# Schematic.net
KiCad netlist of a schematic drawn in EAGLE
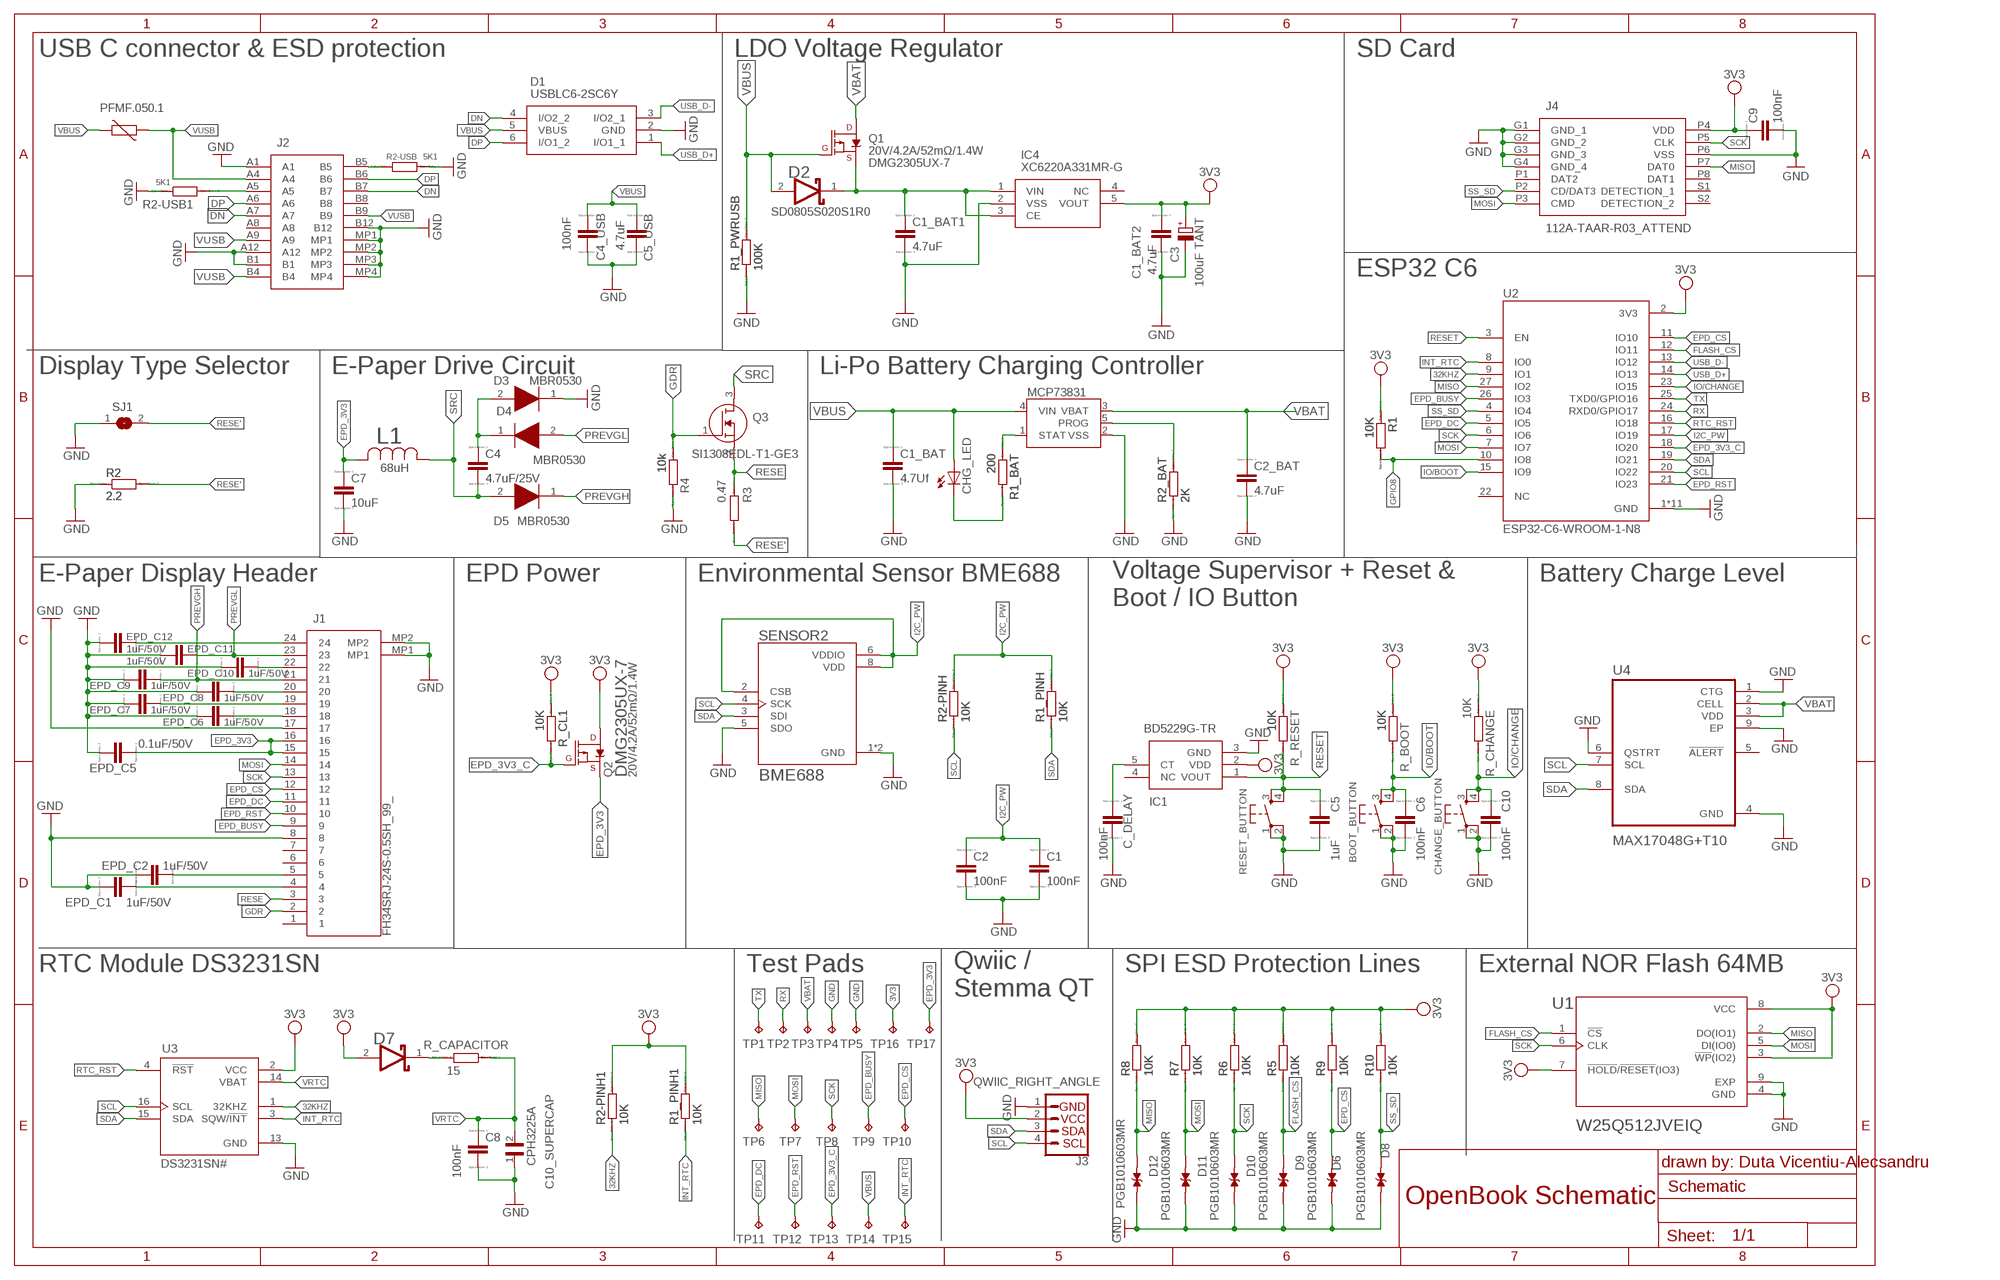
[diagram p0: schematic, sheet 1]

(export (version "E")
  (design (tool "Eeschema 10.0.6"))
  (components
    (comp (ref "BOOT_BUTTON")
      (value "BUTTON_CUSYOMV1")
      (footprint "eagle-import:MYBUTTON")
      (libsource (lib "eagle-import") (part "BUTTON_CUSYOMV1"))
    )
    (comp (ref "C1")
      (value "100nF")
      (footprint "eagle-import:EAGLE-LTSPICE_C0402")
      (libsource (lib "eagle-import") (part "EAGLE-LTSPICE_CC0402"))
    )
    (comp (ref "C1_BAT")
      (value "4.7Uf")
      (footprint "eagle-import:EAGLE-LTSPICE_C0402")
      (libsource (lib "eagle-import") (part "EAGLE-LTSPICE_CC0402"))
    )
    (comp (ref "C1_BAT1")
      (value "4.7uF")
      (footprint "eagle-import:EAGLE-LTSPICE_C0402")
      (libsource (lib "eagle-import") (part "EAGLE-LTSPICE_CC0402"))
    )
    (comp (ref "C1_BAT2")
      (value "4.7uF")
      (footprint "eagle-import:EAGLE-LTSPICE_C0402")
      (libsource (lib "eagle-import") (part "EAGLE-LTSPICE_CC0402"))
    )
    (comp (ref "C2")
      (value "100nF")
      (footprint "eagle-import:EAGLE-LTSPICE_C0402")
      (libsource (lib "eagle-import") (part "EAGLE-LTSPICE_CC0402"))
    )
    (comp (ref "C2_BAT")
      (value "4.7uF")
      (footprint "eagle-import:EAGLE-LTSPICE_C0402")
      (libsource (lib "eagle-import") (part "EAGLE-LTSPICE_CC0402"))
    )
    (comp (ref "C3")
      (value "100uF TANT")
      (footprint "eagle-import:RCL_CT3528")
      (libsource (lib "eagle-import") (part "RCL_CPOL-EUCT3528"))
    )
    (comp (ref "C4")
      (value "4.7uF/25V")
      (footprint "eagle-import:EAGLE-LTSPICE_C0402")
      (libsource (lib "eagle-import") (part "EAGLE-LTSPICE_CC0402"))
    )
    (comp (ref "C4_USB")
      (value "100nF")
      (footprint "eagle-import:EAGLE-LTSPICE_C0402")
      (libsource (lib "eagle-import") (part "EAGLE-LTSPICE_CC0402"))
    )
    (comp (ref "C5")
      (value "1uF")
      (footprint "eagle-import:EAGLE-LTSPICE_C0402")
      (libsource (lib "eagle-import") (part "EAGLE-LTSPICE_CC0402"))
    )
    (comp (ref "C5_USB")
      (value "4.7uF")
      (footprint "eagle-import:EAGLE-LTSPICE_C0402")
      (libsource (lib "eagle-import") (part "EAGLE-LTSPICE_CC0402"))
    )
    (comp (ref "C6")
      (value "100nF")
      (footprint "eagle-import:EAGLE-LTSPICE_C0402")
      (libsource (lib "eagle-import") (part "EAGLE-LTSPICE_CC0402"))
    )
    (comp (ref "C7")
      (value "10uF")
      (footprint "eagle-import:EAGLE-LTSPICE_C0402")
      (libsource (lib "eagle-import") (part "EAGLE-LTSPICE_CC0402"))
    )
    (comp (ref "C8")
      (value "100nF")
      (footprint "eagle-import:EAGLE-LTSPICE_C0402")
      (libsource (lib "eagle-import") (part "EAGLE-LTSPICE_CC0402"))
    )
    (comp (ref "C9")
      (value "100nF")
      (footprint "eagle-import:EAGLE-LTSPICE_C0402")
      (libsource (lib "eagle-import") (part "EAGLE-LTSPICE_CC0402"))
    )
    (comp (ref "C10")
      (value "100nF")
      (footprint "eagle-import:EAGLE-LTSPICE_C0402")
      (libsource (lib "eagle-import") (part "EAGLE-LTSPICE_CC0402"))
    )
    (comp (ref "C10_SUPERCAP")
      (value "CPH3225A")
      (footprint "eagle-import:CAPCP3225X100N")
      (fields (field (name "MF") "Seiko Instruments"))
      (libsource (lib "eagle-import") (part "CPH3225A"))
    )
    (comp (ref "CHANGE_BUTTON")
      (value "BUTTON_CUSYOMV1")
      (footprint "eagle-import:MYBUTTON")
      (libsource (lib "eagle-import") (part "BUTTON_CUSYOMV1"))
    )
    (comp (ref "CHG_LED")
      (value "ADAFRUIT_LEDCHIP-LED0603")
      (footprint "eagle-import:ADAFRUIT_CHIP-LED0603")
      (libsource (lib "eagle-import") (part "ADAFRUIT_LEDCHIP-LED0603"))
    )
    (comp (ref "C_DELAY")
      (value "100nF")
      (footprint "eagle-import:EAGLE-LTSPICE_C0402")
      (libsource (lib "eagle-import") (part "EAGLE-LTSPICE_CC0402"))
    )
    (comp (ref "D1")
      (value "USBLC6-2SC6Y")
      (footprint "eagle-import:SOT95P280X145-6N")
      (fields (field (name "MF") "STMicroelectronics"))
      (libsource (lib "eagle-import") (part "USBLC6-2SC6Y"))
    )
    (comp (ref "D2")
      (value "ESP32_WROVER_AVX---SD0805S020S1R0_AVX_SD0805S020S1R0_0_0AVX_SD0805S020S1R0_0_0")
      (footprint "eagle-import:ESP32_WROVER_AVX---SD0805S020S1R0_AVX_SD0805S020S1R0_0")
      (fields
        (field (name "DIGIKEY_PART_NUMBER") "478-7800-1-ND")
        (field (name "MF") "AVX")
        (field (name "MOUSER_PART_NUMBER") "581-SD0805S020S1R0")
      )
      (libsource (lib "eagle-import") (part "ESP32_WROVER_AVX---SD0805S020S1R0_AVX_SD0805S020S1R0_0_0AVX_SD0805S020S1R0_0_0"))
    )
    (comp (ref "D3")
      (value "MBR0530")
      (footprint "eagle-import:SOD3716X135N")
      (fields (field (name "MF") "ON Semiconductor"))
      (libsource (lib "eagle-import") (part "MBR0530"))
    )
    (comp (ref "D4")
      (value "MBR0530")
      (footprint "eagle-import:SOD3716X135N")
      (fields (field (name "MF") "ON Semiconductor"))
      (libsource (lib "eagle-import") (part "MBR0530"))
    )
    (comp (ref "D5")
      (value "MBR0530")
      (footprint "eagle-import:SOD3716X135N")
      (fields (field (name "MF") "ON Semiconductor"))
      (libsource (lib "eagle-import") (part "MBR0530"))
    )
    (comp (ref "D6")
      (value "PGB1010603MR")
      (footprint "eagle-import:DIOC1608X36N")
      (fields (field (name "MF") "Littelfuse Inc."))
      (libsource (lib "eagle-import") (part "PGB1010603MR"))
    )
    (comp (ref "D7")
      (value "ESP32_WROVER_AVX---SD0805S020S1R0_AVX_SD0805S020S1R0_0_0AVX_SD0805S020S1R0_0_0")
      (footprint "eagle-import:ESP32_WROVER_AVX---SD0805S020S1R0_AVX_SD0805S020S1R0_0")
      (fields
        (field (name "DIGIKEY_PART_NUMBER") "478-7800-1-ND")
        (field (name "MF") "AVX")
        (field (name "MOUSER_PART_NUMBER") "581-SD0805S020S1R0")
      )
      (libsource (lib "eagle-import") (part "ESP32_WROVER_AVX---SD0805S020S1R0_AVX_SD0805S020S1R0_0_0AVX_SD0805S020S1R0_0_0"))
    )
    (comp (ref "D8")
      (value "PGB1010603MR")
      (footprint "eagle-import:DIOC1608X36N")
      (fields (field (name "MF") "Littelfuse Inc."))
      (libsource (lib "eagle-import") (part "PGB1010603MR"))
    )
    (comp (ref "D9")
      (value "PGB1010603MR")
      (footprint "eagle-import:DIOC1608X36N")
      (fields (field (name "MF") "Littelfuse Inc."))
      (libsource (lib "eagle-import") (part "PGB1010603MR"))
    )
    (comp (ref "D10")
      (value "PGB1010603MR")
      (footprint "eagle-import:DIOC1608X36N")
      (fields (field (name "MF") "Littelfuse Inc."))
      (libsource (lib "eagle-import") (part "PGB1010603MR"))
    )
    (comp (ref "D11")
      (value "PGB1010603MR")
      (footprint "eagle-import:DIOC1608X36N")
      (fields (field (name "MF") "Littelfuse Inc."))
      (libsource (lib "eagle-import") (part "PGB1010603MR"))
    )
    (comp (ref "D12")
      (value "PGB1010603MR")
      (footprint "eagle-import:DIOC1608X36N")
      (fields (field (name "MF") "Littelfuse Inc."))
      (libsource (lib "eagle-import") (part "PGB1010603MR"))
    )
    (comp (ref "EPD_C1")
      (value "1uF/50V")
      (footprint "eagle-import:EAGLE-LTSPICE_C0402")
      (libsource (lib "eagle-import") (part "EAGLE-LTSPICE_CC0402"))
    )
    (comp (ref "EPD_C2")
      (value "1uF/50V")
      (footprint "eagle-import:EAGLE-LTSPICE_C0402")
      (libsource (lib "eagle-import") (part "EAGLE-LTSPICE_CC0402"))
    )
    (comp (ref "EPD_C5")
      (value "0.1uF/50V")
      (footprint "eagle-import:EAGLE-LTSPICE_C0402")
      (libsource (lib "eagle-import") (part "EAGLE-LTSPICE_CC0402"))
    )
    (comp (ref "EPD_C6")
      (value "1uF/50V")
      (footprint "eagle-import:EAGLE-LTSPICE_C0402")
      (libsource (lib "eagle-import") (part "EAGLE-LTSPICE_CC0402"))
    )
    (comp (ref "EPD_C7")
      (value "1uF/50V")
      (footprint "eagle-import:EAGLE-LTSPICE_C0402")
      (libsource (lib "eagle-import") (part "EAGLE-LTSPICE_CC0402"))
    )
    (comp (ref "EPD_C8")
      (value "1uF/50V")
      (footprint "eagle-import:EAGLE-LTSPICE_C0402")
      (libsource (lib "eagle-import") (part "EAGLE-LTSPICE_CC0402"))
    )
    (comp (ref "EPD_C9")
      (value "1uF/50V")
      (footprint "eagle-import:EAGLE-LTSPICE_C0402")
      (libsource (lib "eagle-import") (part "EAGLE-LTSPICE_CC0402"))
    )
    (comp (ref "EPD_C10")
      (value "1uF/50V")
      (footprint "eagle-import:EAGLE-LTSPICE_C0402")
      (libsource (lib "eagle-import") (part "EAGLE-LTSPICE_CC0402"))
    )
    (comp (ref "EPD_C11")
      (value "1uF/50V")
      (footprint "eagle-import:EAGLE-LTSPICE_C0402")
      (libsource (lib "eagle-import") (part "EAGLE-LTSPICE_CC0402"))
    )
    (comp (ref "EPD_C12")
      (value "1uF/50V")
      (footprint "eagle-import:EAGLE-LTSPICE_C0402")
      (libsource (lib "eagle-import") (part "EAGLE-LTSPICE_CC0402"))
    )
    (comp (ref "IC1")
      (value "BD5229G-TR")
      (footprint "eagle-import:SOT95P280X125-5N")
      (fields (field (name "MOUSER_PART_NUMBER") "755-BD5229G-TR"))
      (libsource (lib "eagle-import") (part "BD5229G-TR"))
    )
    (comp (ref "IC4")
      (value "XC6220A331MR-G")
      (footprint "eagle-import:SOT95P280X120-5N")
      (fields (field (name "MOUSER_PART_NUMBER") "865-XC6220A331MR-G"))
      (libsource (lib "eagle-import") (part "XC6220A331MR-G"))
    )
    (comp (ref "J1")
      (value "FH34SRJ-24S-0.5SH_99_")
      (footprint "eagle-import:FH34SRJ24S05SH99")
      (fields
        (field (name "MANUFACTURER_PART_NUMBER") "FH34SRJ-24S-0.5SH(99)")
        (field (name "MOUSER_PART_NUMBER") "798-FH34SRJ24S05SH99")
      )
      (libsource (lib "eagle-import") (part "FH34SRJ-24S-0.5SH_99_"))
    )
    (comp (ref "J2")
      (value "SAMACSYS_PARTS_USB4110-GF-A")
      (footprint "eagle-import:SAMACSYS_PARTS_USB4110GFA")
      (fields
        (field (name "MANUFACTURER_PART_NUMBER") "USB4110-GF-A")
        (field (name "MOUSER_PART_NUMBER") "640-USB4110-GF-A")
      )
      (libsource (lib "eagle-import") (part "SAMACSYS_PARTS_USB4110-GF-A"))
    )
    (comp (ref "J3")
      (value "QWIIC_RIGHT_ANGLE")
      (footprint "eagle-import:JST04_1MM_RA")
      (libsource (lib "eagle-import") (part "QWIIC_CONNECTORJS-1MM"))
    )
    (comp (ref "J4")
      (value "112A-TAAR-R03_ATTEND")
      (footprint "eagle-import:112ATAARR03ATTEND")
      (fields (field (name "MANUFACTURER_PART_NUMBER") "112A-TAAR-R03 ATTEND"))
      (libsource (lib "eagle-import") (part "112A-TAAR-R03_ATTEND"))
    )
    (comp (ref "L1")
      (value "744043680IND_4828-WE-TPC_WRE")
      (footprint "eagle-import:IND_4828-WE-TPC_WRE")
      (fields
        (field (name "MANUFACTURER_PART_NUMBER") "744043680")
        (field (name "COPYRIGHT") "Copyright (C) 2024 Ultra Librarian. All rights reserved.")
      )
      (libsource (lib "eagle-import") (part "744043680IND_4828-WE-TPC_WRE"))
    )
    (comp (ref "MCP73831")
      (value "ESP32_WROVER_SPARKFUN-IC-POWER_MCP73831")
      (footprint "eagle-import:ESP32_WROVER_SPARKFUN-IC-POWER_SOT23-5")
      (libsource (lib "eagle-import") (part "ESP32_WROVER_SPARKFUN-IC-POWER_MCP73831"))
    )
    (comp (ref "PFMF.050.1")
      (value "ESP32C6_VARISTORCN1812")
      (footprint "eagle-import:ESP32C6_VARISTOR_CT_CN1812")
      (libsource (lib "eagle-import") (part "ESP32C6_VARISTORCN1812"))
    )
    (comp (ref "Q1")
      (value "20V/4.2A/52mΩ/1.4W")
      (footprint "eagle-import:ESP32_WROVER_SPARKFUN-DISCRETESEMI_SOT23-3")
      (libsource (lib "eagle-import") (part "ESP32_WROVER_SPARKFUN-DISCRETESEMI_MOSFET_PCH-DMG2305UX-7"))
    )
    (comp (ref "Q2")
      (value "20V/4.2A/52mΩ/1.4W")
      (footprint "eagle-import:ESP32_WROVER_SPARKFUN-DISCRETESEMI_SOT23-3")
      (libsource (lib "eagle-import") (part "ESP32_WROVER_SPARKFUN-DISCRETESEMI_MOSFET_PCH-DMG2305UX-7"))
    )
    (comp (ref "Q3")
      (value "SI1308EDL-T1-GE3")
      (footprint "eagle-import:SOT65P210X110-3N")
      (fields (field (name "MF") "Vishay Siliconix"))
      (libsource (lib "eagle-import") (part "SI1308EDL-T1-GE3"))
    )
    (comp (ref "R1")
      (value "10K")
      (footprint "eagle-import:ESP32_WROVER_EAGLE-LTSPICE_R0402")
      (libsource (lib "eagle-import") (part "ESP32_WROVER_EAGLE-LTSPICE_RR0402"))
    )
    (comp (ref "R1_BAT")
      (value "200")
      (footprint "eagle-import:ESP32_WROVER_EAGLE-LTSPICE_R0402")
      (libsource (lib "eagle-import") (part "ESP32_WROVER_EAGLE-LTSPICE_RR0402"))
    )
    (comp (ref "R1_PINH")
      (value "10K")
      (footprint "eagle-import:ESP32_WROVER_EAGLE-LTSPICE_R0402")
      (libsource (lib "eagle-import") (part "ESP32_WROVER_EAGLE-LTSPICE_RR0402"))
    )
    (comp (ref "R1_PINH1")
      (value "10K")
      (footprint "eagle-import:ESP32_WROVER_EAGLE-LTSPICE_R0402")
      (libsource (lib "eagle-import") (part "ESP32_WROVER_EAGLE-LTSPICE_RR0402"))
    )
    (comp (ref "R1_PWRUSB")
      (value "100K")
      (footprint "eagle-import:ESP32_WROVER_EAGLE-LTSPICE_R0402")
      (libsource (lib "eagle-import") (part "ESP32_WROVER_EAGLE-LTSPICE_RR0402"))
    )
    (comp (ref "R2")
      (value "2.2")
      (footprint "eagle-import:ESP32_WROVER_EAGLE-LTSPICE_R0402")
      (libsource (lib "eagle-import") (part "ESP32_WROVER_EAGLE-LTSPICE_RR0402"))
    )
    (comp (ref "R2-PINH")
      (value "10K")
      (footprint "eagle-import:ESP32_WROVER_EAGLE-LTSPICE_R0402")
      (libsource (lib "eagle-import") (part "ESP32_WROVER_EAGLE-LTSPICE_RR0402"))
    )
    (comp (ref "R2-PINH1")
      (value "10K")
      (footprint "eagle-import:ESP32_WROVER_EAGLE-LTSPICE_R0402")
      (libsource (lib "eagle-import") (part "ESP32_WROVER_EAGLE-LTSPICE_RR0402"))
    )
    (comp (ref "R2-USB")
      (value "5K1")
      (footprint "eagle-import:ESP32_WROVER_EAGLE-LTSPICE_R0402")
      (libsource (lib "eagle-import") (part "ESP32_WROVER_EAGLE-LTSPICE_RR0402"))
    )
    (comp (ref "R2-USB1")
      (value "5K1")
      (footprint "eagle-import:ESP32_WROVER_EAGLE-LTSPICE_R0402")
      (libsource (lib "eagle-import") (part "ESP32_WROVER_EAGLE-LTSPICE_RR0402"))
    )
    (comp (ref "R2_BAT")
      (value "2K")
      (footprint "eagle-import:ESP32_WROVER_EAGLE-LTSPICE_R0402")
      (libsource (lib "eagle-import") (part "ESP32_WROVER_EAGLE-LTSPICE_RR0402"))
    )
    (comp (ref "R3")
      (value "0.47")
      (footprint "eagle-import:ESP32_WROVER_EAGLE-LTSPICE_R0402")
      (libsource (lib "eagle-import") (part "ESP32_WROVER_EAGLE-LTSPICE_RR0402"))
    )
    (comp (ref "R4")
      (value "10k")
      (footprint "eagle-import:ESP32_WROVER_EAGLE-LTSPICE_R0402")
      (libsource (lib "eagle-import") (part "ESP32_WROVER_EAGLE-LTSPICE_RR0402"))
    )
    (comp (ref "R5")
      (value "10K")
      (footprint "eagle-import:ESP32_WROVER_EAGLE-LTSPICE_R0402")
      (libsource (lib "eagle-import") (part "ESP32_WROVER_EAGLE-LTSPICE_RR0402"))
    )
    (comp (ref "R6")
      (value "10K")
      (footprint "eagle-import:ESP32_WROVER_EAGLE-LTSPICE_R0402")
      (libsource (lib "eagle-import") (part "ESP32_WROVER_EAGLE-LTSPICE_RR0402"))
    )
    (comp (ref "R7")
      (value "10K")
      (footprint "eagle-import:ESP32_WROVER_EAGLE-LTSPICE_R0402")
      (libsource (lib "eagle-import") (part "ESP32_WROVER_EAGLE-LTSPICE_RR0402"))
    )
    (comp (ref "R8")
      (value "10K")
      (footprint "eagle-import:ESP32_WROVER_EAGLE-LTSPICE_R0402")
      (libsource (lib "eagle-import") (part "ESP32_WROVER_EAGLE-LTSPICE_RR0402"))
    )
    (comp (ref "R9")
      (value "10K")
      (footprint "eagle-import:ESP32_WROVER_EAGLE-LTSPICE_R0402")
      (libsource (lib "eagle-import") (part "ESP32_WROVER_EAGLE-LTSPICE_RR0402"))
    )
    (comp (ref "R10")
      (value "10K")
      (footprint "eagle-import:ESP32_WROVER_EAGLE-LTSPICE_R0402")
      (libsource (lib "eagle-import") (part "ESP32_WROVER_EAGLE-LTSPICE_RR0402"))
    )
    (comp (ref "RESET_BUTTON")
      (value "BUTTON_CUSYOMV1")
      (footprint "eagle-import:MYBUTTON")
      (libsource (lib "eagle-import") (part "BUTTON_CUSYOMV1"))
    )
    (comp (ref "R_BOOT")
      (value "10K")
      (footprint "eagle-import:ESP32_WROVER_EAGLE-LTSPICE_R0402")
      (libsource (lib "eagle-import") (part "ESP32_WROVER_EAGLE-LTSPICE_RR0402"))
    )
    (comp (ref "R_CAPACITOR")
      (value "15")
      (footprint "eagle-import:ESP32_WROVER_EAGLE-LTSPICE_R0402")
      (libsource (lib "eagle-import") (part "ESP32_WROVER_EAGLE-LTSPICE_RR0402"))
    )
    (comp (ref "R_CHANGE")
      (value "10K")
      (footprint "eagle-import:ESP32_WROVER_EAGLE-LTSPICE_R0402")
      (libsource (lib "eagle-import") (part "ESP32_WROVER_EAGLE-LTSPICE_RR0402"))
    )
    (comp (ref "R_CL1")
      (value "10K")
      (footprint "eagle-import:ESP32_WROVER_EAGLE-LTSPICE_R0402")
      (libsource (lib "eagle-import") (part "ESP32_WROVER_EAGLE-LTSPICE_RR0402"))
    )
    (comp (ref "R_RESET")
      (value "10K")
      (footprint "eagle-import:ESP32_WROVER_EAGLE-LTSPICE_R0402")
      (libsource (lib "eagle-import") (part "ESP32_WROVER_EAGLE-LTSPICE_RR0402"))
    )
    (comp (ref "SENSOR2")
      (value "ESP32_WROVER_BME680_BME680")
      (footprint "eagle-import:ESP32_WROVER_BME680_PSON80P300X300X100-8N")
      (fields (field (name "MF") "Bosch Sensortec") (field (name "MP") "BME680"))
      (libsource (lib "eagle-import") (part "ESP32_WROVER_BME680_BME680"))
    )
    (comp (ref "SJ1") (value "SJ") (footprint "eagle-import:SJ") (libsource (lib "eagle-import") (part "SJ")))
    (comp (ref "TP1")
      (value "TPTP20R")
      (footprint "eagle-import:TP20R")
      (libsource (lib "eagle-import") (part "TPTP20R"))
    )
    (comp (ref "TP2")
      (value "TPTP20R")
      (footprint "eagle-import:TP20R")
      (libsource (lib "eagle-import") (part "TPTP20R"))
    )
    (comp (ref "TP3")
      (value "TPTP20R")
      (footprint "eagle-import:TP20R")
      (libsource (lib "eagle-import") (part "TPTP20R"))
    )
    (comp (ref "TP4")
      (value "TPTP20R")
      (footprint "eagle-import:TP20R")
      (libsource (lib "eagle-import") (part "TPTP20R"))
    )
    (comp (ref "TP5")
      (value "TPTP20R")
      (footprint "eagle-import:TP20R")
      (libsource (lib "eagle-import") (part "TPTP20R"))
    )
    (comp (ref "TP6")
      (value "TPTP20R")
      (footprint "eagle-import:TP20R")
      (libsource (lib "eagle-import") (part "TPTP20R"))
    )
    (comp (ref "TP7")
      (value "TPTP20R")
      (footprint "eagle-import:TP20R")
      (libsource (lib "eagle-import") (part "TPTP20R"))
    )
    (comp (ref "TP8")
      (value "TPTP20R")
      (footprint "eagle-import:TP20R")
      (libsource (lib "eagle-import") (part "TPTP20R"))
    )
    (comp (ref "TP9")
      (value "TPTP20R")
      (footprint "eagle-import:TP20R")
      (libsource (lib "eagle-import") (part "TPTP20R"))
    )
    (comp (ref "TP10")
      (value "TPTP20R")
      (footprint "eagle-import:TP20R")
      (libsource (lib "eagle-import") (part "TPTP20R"))
    )
    (comp (ref "TP11")
      (value "TPTP20R")
      (footprint "eagle-import:TP20R")
      (libsource (lib "eagle-import") (part "TPTP20R"))
    )
    (comp (ref "TP12")
      (value "TPTP20R")
      (footprint "eagle-import:TP20R")
      (libsource (lib "eagle-import") (part "TPTP20R"))
    )
    (comp (ref "TP13")
      (value "TPTP20R")
      (footprint "eagle-import:TP20R")
      (libsource (lib "eagle-import") (part "TPTP20R"))
    )
    (comp (ref "TP14")
      (value "TPTP20R")
      (footprint "eagle-import:TP20R")
      (libsource (lib "eagle-import") (part "TPTP20R"))
    )
    (comp (ref "TP15")
      (value "TPTP20R")
      (footprint "eagle-import:TP20R")
      (libsource (lib "eagle-import") (part "TPTP20R"))
    )
    (comp (ref "TP16")
      (value "TPTP20R")
      (footprint "eagle-import:TP20R")
      (libsource (lib "eagle-import") (part "TPTP20R"))
    )
    (comp (ref "TP17")
      (value "TPTP20R")
      (footprint "eagle-import:TP20R")
      (libsource (lib "eagle-import") (part "TPTP20R"))
    )
    (comp (ref "U1")
      (value "W25Q512JVEIQ")
      (footprint "eagle-import:SON127P600X800X80-9N")
      (fields (field (name "MF") "Winbond Electronics"))
      (libsource (lib "eagle-import") (part "W25Q512JVEIQ"))
    )
    (comp (ref "U2")
      (value "ESP32-C6-WROOM-1-N8")
      (footprint "eagle-import:XCVR_ESP32-C6-WROOM-1-N8")
      (fields (field (name "MF") "Espressif Systems"))
      (libsource (lib "eagle-import") (part "ESP32-C6-WROOM-1-N8"))
    )
    (comp (ref "U3")
      (value "DS3231SN#")
      (footprint "eagle-import:SOIC127P1032X265-16N")
      (fields (field (name "MF") "Analog Devices"))
      (libsource (lib "eagle-import") (part "DS3231SN#"))
    )
    (comp (ref "U4")
      (value "MAX17048G+T10")
      (footprint "eagle-import:SON50P200X200X80-9N")
      (fields (field (name "MF") "Analog Devices"))
      (libsource (lib "eagle-import") (part "MAX17048G+T10"))
    )
  )
  (nets
    (net (code "1") (name "3V3") (class "Default")
      (node (ref "C1_BAT2") (pin "1") (pinfunction "1_1") (pintype "passive"))
      (node (ref "C3") (pin "+") (pinfunction "+_+") (pintype "passive"))
      (node (ref "C9") (pin "1") (pinfunction "1_1") (pintype "passive"))
      (node (ref "D7") (pin "2") (pinfunction "ANODE_2") (pintype "bidirectional"))
      (node (ref "IC1") (pin "2") (pinfunction "VDD_2") (pintype "bidirectional"))
      (node (ref "IC4") (pin "5") (pinfunction "VOUT_5") (pintype "bidirectional"))
      (node (ref "J3") (pin "2") (pinfunction "2_2") (pintype "power_in"))
      (node (ref "J4") (pin "P4") (pinfunction "VDD_P4") (pintype "bidirectional"))
      (node (ref "Q2") (pin "3") (pinfunction "D_3") (pintype "bidirectional"))
      (node (ref "R1") (pin "1") (pinfunction "1_1") (pintype "passive"))
      (node (ref "R10") (pin "2") (pinfunction "2_2") (pintype "passive"))
      (node (ref "R1_PINH1") (pin "2") (pinfunction "2_2") (pintype "passive"))
      (node (ref "R2-PINH1") (pin "2") (pinfunction "2_2") (pintype "passive"))
      (node (ref "R5") (pin "2") (pinfunction "2_2") (pintype "passive"))
      (node (ref "R6") (pin "2") (pinfunction "2_2") (pintype "passive"))
      (node (ref "R7") (pin "2") (pinfunction "2_2") (pintype "passive"))
      (node (ref "R8") (pin "2") (pinfunction "2_2") (pintype "passive"))
      (node (ref "R9") (pin "2") (pinfunction "2_2") (pintype "passive"))
      (node (ref "R_BOOT") (pin "1") (pinfunction "1_1") (pintype "passive"))
      (node (ref "R_CHANGE") (pin "1") (pinfunction "1_1") (pintype "passive"))
      (node (ref "R_CL1") (pin "1") (pinfunction "1_1") (pintype "passive"))
      (node (ref "R_RESET") (pin "1") (pinfunction "1_1") (pintype "passive"))
      (node (ref "TP16") (pin "TP") (pinfunction "TP_TP") (pintype "input"))
      (node (ref "U1") (pin "3") (pinfunction "~{WP}(IO2)_3") (pintype "bidirectional"))
      (node (ref "U1") (pin "7") (pinfunction "~{HOLD}/~{RESET}(IO3)_7") (pintype "bidirectional"))
      (node (ref "U1") (pin "8") (pinfunction "VCC_8") (pintype "power_in"))
      (node (ref "U2") (pin "2") (pinfunction "3V3_2") (pintype "power_in"))
      (node (ref "U3") (pin "2") (pinfunction "VCC_2") (pintype "power_in"))
    )
    (net (code "2") (name "32KHZ") (class "Default")
      (node (ref "R2-PINH1") (pin "1") (pinfunction "1_1") (pintype "passive"))
      (node (ref "U2") (pin "9") (pinfunction "IO1_9") (pintype "bidirectional"))
      (node (ref "U3") (pin "1") (pinfunction "32KHZ_1") (pintype "output"))
    )
    (net (code "3") (name "DN") (class "Default")
      (node (ref "D1") (pin "4") (pinfunction "I/O2_2_4") (pintype "bidirectional"))
      (node (ref "J2") (pin "A7") (pinfunction "A7_A7") (pintype "bidirectional"))
      (node (ref "J2") (pin "B7") (pinfunction "B7_B7") (pintype "bidirectional"))
    )
    (net (code "4") (name "DP") (class "Default")
      (node (ref "D1") (pin "6") (pinfunction "I/O1_2_6") (pintype "bidirectional"))
      (node (ref "J2") (pin "A6") (pinfunction "A6_A6") (pintype "bidirectional"))
      (node (ref "J2") (pin "B6") (pinfunction "B6_B6") (pintype "bidirectional"))
    )
    (net (code "5") (name "EPD_3V3") (class "Default")
      (node (ref "C7") (pin "1") (pinfunction "1_1") (pintype "passive"))
      (node (ref "EPD_C5") (pin "1") (pinfunction "1_1") (pintype "passive"))
      (node (ref "J1") (pin "15") (pinfunction "15_15") (pintype "bidirectional"))
      (node (ref "J1") (pin "16") (pinfunction "16_16") (pintype "bidirectional"))
      (node (ref "L1") (pin "2") (pinfunction "2_2") (pintype "passive"))
      (node (ref "Q2") (pin "2") (pinfunction "S_2") (pintype "bidirectional"))
      (node (ref "TP17") (pin "TP") (pinfunction "TP_TP") (pintype "input"))
    )
    (net (code "6") (name "EPD_3V3_C") (class "Default")
      (node (ref "Q2") (pin "1") (pinfunction "G_1") (pintype "bidirectional"))
      (node (ref "R_CL1") (pin "2") (pinfunction "2_2") (pintype "passive"))
      (node (ref "TP13") (pin "TP") (pinfunction "TP_TP") (pintype "input"))
      (node (ref "U2") (pin "18") (pinfunction "IO20_18") (pintype "bidirectional"))
    )
    (net (code "7") (name "EPD_BUSY") (class "Default")
      (node (ref "J1") (pin "9") (pinfunction "9_9") (pintype "bidirectional"))
      (node (ref "TP9") (pin "TP") (pinfunction "TP_TP") (pintype "input"))
      (node (ref "U2") (pin "26") (pinfunction "IO3_26") (pintype "bidirectional"))
    )
    (net (code "8") (name "EPD_CS") (class "Default")
      (node (ref "D6") (pin "1") (pinfunction "1_1") (pintype "passive"))
      (node (ref "J1") (pin "12") (pinfunction "12_12") (pintype "bidirectional"))
      (node (ref "R9") (pin "1") (pinfunction "1_1") (pintype "passive"))
      (node (ref "TP10") (pin "TP") (pinfunction "TP_TP") (pintype "input"))
      (node (ref "U2") (pin "11") (pinfunction "IO10_11") (pintype "bidirectional"))
    )
    (net (code "9") (name "EPD_DC") (class "Default")
      (node (ref "J1") (pin "11") (pinfunction "11_11") (pintype "bidirectional"))
      (node (ref "TP11") (pin "TP") (pinfunction "TP_TP") (pintype "input"))
      (node (ref "U2") (pin "5") (pinfunction "IO5_5") (pintype "bidirectional"))
    )
    (net (code "10") (name "EPD_RST") (class "Default")
      (node (ref "J1") (pin "10") (pinfunction "10_10") (pintype "bidirectional"))
      (node (ref "TP12") (pin "TP") (pinfunction "TP_TP") (pintype "input"))
      (node (ref "U2") (pin "21") (pinfunction "IO23_21") (pintype "bidirectional"))
    )
    (net (code "11") (name "FLASH_CS") (class "Default")
      (node (ref "D9") (pin "1") (pinfunction "1_1") (pintype "passive"))
      (node (ref "R5") (pin "1") (pinfunction "1_1") (pintype "passive"))
      (node (ref "U1") (pin "1") (pinfunction "~{CS}_1") (pintype "input"))
      (node (ref "U2") (pin "12") (pinfunction "IO11_12") (pintype "bidirectional"))
    )
    (net (code "12") (name "GDR") (class "Default")
      (node (ref "J1") (pin "2") (pinfunction "2_2") (pintype "bidirectional"))
      (node (ref "Q3") (pin "1") (pinfunction "G_1") (pintype "bidirectional"))
      (node (ref "R4") (pin "1") (pinfunction "1_1") (pintype "passive"))
    )
    (net (code "13") (name "GND") (class "Default")
      (node (ref "BOOT_BUTTON") (pin "1") (pinfunction "1_1") (pintype "passive"))
      (node (ref "BOOT_BUTTON") (pin "2") (pinfunction "2_2") (pintype "passive"))
      (node (ref "C1") (pin "2") (pinfunction "2_2") (pintype "passive"))
      (node (ref "C10") (pin "2") (pinfunction "2_2") (pintype "passive"))
      (node (ref "C10_SUPERCAP") (pin "1") (pinfunction "1_1") (pintype "passive"))
      (node (ref "C1_BAT") (pin "2") (pinfunction "2_2") (pintype "passive"))
      (node (ref "C1_BAT1") (pin "2") (pinfunction "2_2") (pintype "passive"))
      (node (ref "C1_BAT2") (pin "2") (pinfunction "2_2") (pintype "passive"))
      (node (ref "C2") (pin "2") (pinfunction "2_2") (pintype "passive"))
      (node (ref "C2_BAT") (pin "2") (pinfunction "2_2") (pintype "passive"))
      (node (ref "C3") (pin "-") (pinfunction "-_-") (pintype "passive"))
      (node (ref "C4_USB") (pin "2") (pinfunction "2_2") (pintype "passive"))
      (node (ref "C5") (pin "2") (pinfunction "2_2") (pintype "passive"))
      (node (ref "C5_USB") (pin "2") (pinfunction "2_2") (pintype "passive"))
      (node (ref "C6") (pin "2") (pinfunction "2_2") (pintype "passive"))
      (node (ref "C7") (pin "2") (pinfunction "2_2") (pintype "passive"))
      (node (ref "C8") (pin "2") (pinfunction "2_2") (pintype "passive"))
      (node (ref "C9") (pin "2") (pinfunction "2_2") (pintype "passive"))
      (node (ref "CHANGE_BUTTON") (pin "1") (pinfunction "1_1") (pintype "passive"))
      (node (ref "CHANGE_BUTTON") (pin "2") (pinfunction "2_2") (pintype "passive"))
      (node (ref "C_DELAY") (pin "2") (pinfunction "2_2") (pintype "passive"))
      (node (ref "D1") (pin "2") (pinfunction "GND_2") (pintype "bidirectional"))
      (node (ref "D10") (pin "2") (pinfunction "2_2") (pintype "passive"))
      (node (ref "D11") (pin "2") (pinfunction "2_2") (pintype "passive"))
      (node (ref "D12") (pin "2") (pinfunction "2_2") (pintype "passive"))
      (node (ref "D3") (pin "1") (pinfunction "K_1") (pintype "bidirectional"))
      (node (ref "D6") (pin "2") (pinfunction "2_2") (pintype "passive"))
      (node (ref "D8") (pin "2") (pinfunction "2_2") (pintype "passive"))
      (node (ref "D9") (pin "2") (pinfunction "2_2") (pintype "passive"))
      (node (ref "EPD_C1") (pin "2") (pinfunction "2_2") (pintype "passive"))
      (node (ref "EPD_C10") (pin "2") (pinfunction "2_2") (pintype "passive"))
      (node (ref "EPD_C11") (pin "2") (pinfunction "2_2") (pintype "passive"))
      (node (ref "EPD_C12") (pin "2") (pinfunction "2_2") (pintype "passive"))
      (node (ref "EPD_C2") (pin "2") (pinfunction "2_2") (pintype "passive"))
      (node (ref "EPD_C5") (pin "2") (pinfunction "2_2") (pintype "passive"))
      (node (ref "EPD_C6") (pin "2") (pinfunction "2_2") (pintype "passive"))
      (node (ref "EPD_C7") (pin "2") (pinfunction "2_2") (pintype "passive"))
      (node (ref "EPD_C8") (pin "2") (pinfunction "2_2") (pintype "passive"))
      (node (ref "EPD_C9") (pin "2") (pinfunction "2_2") (pintype "passive"))
      (node (ref "IC1") (pin "3") (pinfunction "GND_3") (pintype "bidirectional"))
      (node (ref "IC4") (pin "2") (pinfunction "VSS_2") (pintype "bidirectional"))
      (node (ref "J1") (pin "17") (pinfunction "17_17") (pintype "bidirectional"))
      (node (ref "J1") (pin "8") (pinfunction "8_8") (pintype "bidirectional"))
      (node (ref "J1") (pin "MP1") (pinfunction "MP1_MP1") (pintype "bidirectional"))
      (node (ref "J1") (pin "MP2") (pinfunction "MP2_MP2") (pintype "bidirectional"))
      (node (ref "J2") (pin "A1") (pinfunction "A1_A1") (pintype "bidirectional"))
      (node (ref "J2") (pin "A12") (pinfunction "A12_A12") (pintype "bidirectional"))
      (node (ref "J2") (pin "B1") (pinfunction "B1_B1") (pintype "bidirectional"))
      (node (ref "J2") (pin "B12") (pinfunction "B12_B12") (pintype "bidirectional"))
      (node (ref "J2") (pin "MP1") (pinfunction "MP1_MP1") (pintype "bidirectional"))
      (node (ref "J2") (pin "MP2") (pinfunction "MP2_MP2") (pintype "bidirectional"))
      (node (ref "J2") (pin "MP3") (pinfunction "MP3_MP3") (pintype "bidirectional"))
      (node (ref "J2") (pin "MP4") (pinfunction "MP4_MP4") (pintype "bidirectional"))
      (node (ref "J3") (pin "1") (pinfunction "1_1") (pintype "power_in"))
      (node (ref "J4") (pin "G1") (pinfunction "GND_1_G1") (pintype "bidirectional"))
      (node (ref "J4") (pin "G2") (pinfunction "GND_2_G2") (pintype "bidirectional"))
      (node (ref "J4") (pin "G3") (pinfunction "GND_3_G3") (pintype "bidirectional"))
      (node (ref "J4") (pin "G4") (pinfunction "GND_4_G4") (pintype "bidirectional"))
      (node (ref "J4") (pin "P6") (pinfunction "VSS_P6") (pintype "bidirectional"))
      (node (ref "MCP73831") (pin "2") (pinfunction "VSS_2") (pintype "power_in"))
      (node (ref "R1_PWRUSB") (pin "1") (pinfunction "1_1") (pintype "passive"))
      (node (ref "R2") (pin "1") (pinfunction "1_1") (pintype "passive"))
      (node (ref "R2-USB") (pin "2") (pinfunction "2_2") (pintype "passive"))
      (node (ref "R2-USB1") (pin "1") (pinfunction "1_1") (pintype "passive"))
      (node (ref "R2_BAT") (pin "1") (pinfunction "1_1") (pintype "passive"))
      (node (ref "R4") (pin "2") (pinfunction "2_2") (pintype "passive"))
      (node (ref "RESET_BUTTON") (pin "1") (pinfunction "1_1") (pintype "passive"))
      (node (ref "RESET_BUTTON") (pin "2") (pinfunction "2_2") (pintype "passive"))
      (node (ref "SENSOR2") (pin "1") (pinfunction "GND_1") (pintype "power_in"))
      (node (ref "SENSOR2") (pin "5") (pinfunction "SDO_5") (pintype "bidirectional"))
      (node (ref "SENSOR2") (pin "7") (pinfunction "GND_7") (pintype "power_in"))
      (node (ref "SJ1") (pin "1") (pinfunction "1_1") (pintype "passive"))
      (node (ref "TP4") (pin "TP") (pinfunction "TP_TP") (pintype "input"))
      (node (ref "TP5") (pin "TP") (pinfunction "TP_TP") (pintype "input"))
      (node (ref "U1") (pin "4") (pinfunction "GND_4") (pintype "power_in"))
      (node (ref "U1") (pin "9") (pinfunction "EXP_9") (pintype "passive"))
      (node (ref "U2") (pin "1") (pinfunction "GND_1") (pintype "power_in"))
      (node (ref "U2") (pin "28") (pinfunction "GND_28") (pintype "power_in"))
      (node (ref "U2") (pin "29_1") (pinfunction "GND_29_1") (pintype "power_in"))
      (node (ref "U2") (pin "29_2") (pinfunction "GND_29_2") (pintype "power_in"))
      (node (ref "U2") (pin "29_3") (pinfunction "GND_29_3") (pintype "power_in"))
      (node (ref "U2") (pin "29_4") (pinfunction "GND_29_4") (pintype "power_in"))
      (node (ref "U2") (pin "29_5") (pinfunction "GND_29_5") (pintype "power_in"))
      (node (ref "U2") (pin "29_6") (pinfunction "GND_29_6") (pintype "power_in"))
      (node (ref "U2") (pin "29_7") (pinfunction "GND_29_7") (pintype "power_in"))
      (node (ref "U2") (pin "29_8") (pinfunction "GND_29_8") (pintype "power_in"))
      (node (ref "U2") (pin "29_9") (pinfunction "GND_29_9") (pintype "power_in"))
      (node (ref "U3") (pin "13") (pinfunction "GND_13") (pintype "power_in"))
      (node (ref "U4") (pin "1") (pinfunction "CTG_1") (pintype "power_in"))
      (node (ref "U4") (pin "4") (pinfunction "GND_4") (pintype "power_in"))
      (node (ref "U4") (pin "6") (pinfunction "QSTRT_6") (pintype "input"))
      (node (ref "U4") (pin "9") (pinfunction "EP_9") (pintype "power_in"))
    )
    (net (code "14") (name "GPIO8") (class "Default")
      (node (ref "R1") (pin "2") (pinfunction "2_2") (pintype "passive"))
      (node (ref "U2") (pin "10") (pinfunction "IO8_10") (pintype "bidirectional"))
    )
    (net (code "15") (name "I2C_PW") (class "Default")
      (node (ref "C1") (pin "1") (pinfunction "1_1") (pintype "passive"))
      (node (ref "C2") (pin "1") (pinfunction "1_1") (pintype "passive"))
      (node (ref "R1_PINH") (pin "2") (pinfunction "2_2") (pintype "passive"))
      (node (ref "R2-PINH") (pin "2") (pinfunction "2_2") (pintype "passive"))
      (node (ref "SENSOR2") (pin "2") (pinfunction "CSB_2") (pintype "input"))
      (node (ref "SENSOR2") (pin "6") (pinfunction "VDDIO_6") (pintype "power_in"))
      (node (ref "SENSOR2") (pin "8") (pinfunction "VDD_8") (pintype "power_in"))
      (node (ref "U2") (pin "17") (pinfunction "IO19_17") (pintype "bidirectional"))
    )
    (net (code "16") (name "INT_RTC") (class "Default")
      (node (ref "R1_PINH1") (pin "1") (pinfunction "1_1") (pintype "passive"))
      (node (ref "TP15") (pin "TP") (pinfunction "TP_TP") (pintype "input"))
      (node (ref "U2") (pin "8") (pinfunction "IO0_8") (pintype "bidirectional"))
      (node (ref "U3") (pin "3") (pinfunction "SQW/~{INT}_3") (pintype "output"))
    )
    (net (code "17") (name "IO{slash}BOOT") (class "Default")
      (node (ref "BOOT_BUTTON") (pin "3") (pinfunction "3_3") (pintype "passive"))
      (node (ref "BOOT_BUTTON") (pin "4") (pinfunction "4_4") (pintype "passive"))
      (node (ref "C6") (pin "1") (pinfunction "1_1") (pintype "passive"))
      (node (ref "R_BOOT") (pin "2") (pinfunction "2_2") (pintype "passive"))
      (node (ref "U2") (pin "15") (pinfunction "IO9_15") (pintype "bidirectional"))
    )
    (net (code "18") (name "IO{slash}CHANGE") (class "Default")
      (node (ref "C10") (pin "1") (pinfunction "1_1") (pintype "passive"))
      (node (ref "CHANGE_BUTTON") (pin "3") (pinfunction "3_3") (pintype "passive"))
      (node (ref "CHANGE_BUTTON") (pin "4") (pinfunction "4_4") (pintype "passive"))
      (node (ref "R_CHANGE") (pin "2") (pinfunction "2_2") (pintype "passive"))
      (node (ref "U2") (pin "23") (pinfunction "IO15_23") (pintype "bidirectional"))
    )
    (net (code "19") (name "MISO") (class "Default")
      (node (ref "D12") (pin "1") (pinfunction "1_1") (pintype "passive"))
      (node (ref "J4") (pin "P7") (pinfunction "DAT0_P7") (pintype "bidirectional"))
      (node (ref "R8") (pin "1") (pinfunction "1_1") (pintype "passive"))
      (node (ref "TP6") (pin "TP") (pinfunction "TP_TP") (pintype "input"))
      (node (ref "U1") (pin "2") (pinfunction "DO(IO1)_2") (pintype "bidirectional"))
      (node (ref "U2") (pin "27") (pinfunction "IO2_27") (pintype "bidirectional"))
    )
    (net (code "20") (name "MOSI") (class "Default")
      (node (ref "D11") (pin "1") (pinfunction "1_1") (pintype "passive"))
      (node (ref "J1") (pin "14") (pinfunction "14_14") (pintype "bidirectional"))
      (node (ref "J4") (pin "P3") (pinfunction "CMD_P3") (pintype "bidirectional"))
      (node (ref "R7") (pin "1") (pinfunction "1_1") (pintype "passive"))
      (node (ref "TP7") (pin "TP") (pinfunction "TP_TP") (pintype "input"))
      (node (ref "U1") (pin "5") (pinfunction "DI(IO0)_5") (pintype "bidirectional"))
      (node (ref "U2") (pin "7") (pinfunction "IO7_7") (pintype "bidirectional"))
    )
    (net (code "21") (name "Net-(CHG_LED-PadC)") (class "Default")
      (node (ref "CHG_LED") (pin "C") (pinfunction "C_C") (pintype "passive"))
      (node (ref "R1_BAT") (pin "2") (pinfunction "2_2") (pintype "passive"))
    )
    (net (code "22") (name "Net-(D2-CATHODE)") (class "Default")
      (node (ref "C1_BAT1") (pin "1") (pinfunction "1_1") (pintype "passive"))
      (node (ref "D2") (pin "1") (pinfunction "CATHODE_1") (pintype "bidirectional"))
      (node (ref "IC4") (pin "1") (pinfunction "VIN_1") (pintype "bidirectional"))
      (node (ref "IC4") (pin "3") (pinfunction "CE_3") (pintype "bidirectional"))
      (node (ref "Q1") (pin "2") (pinfunction "S_2") (pintype "bidirectional"))
    )
    (net (code "23") (name "Net-(D3-A)") (class "Default")
      (node (ref "C4") (pin "1") (pinfunction "1_1") (pintype "passive"))
      (node (ref "D3") (pin "2") (pinfunction "A_2") (pintype "bidirectional"))
      (node (ref "D4") (pin "1") (pinfunction "K_1") (pintype "bidirectional"))
    )
    (net (code "24") (name "Net-(D7-CATHODE)") (class "Default")
      (node (ref "D7") (pin "1") (pinfunction "CATHODE_1") (pintype "bidirectional"))
      (node (ref "R_CAPACITOR") (pin "2") (pinfunction "2_2") (pintype "passive"))
    )
    (net (code "25") (name "Net-(EPD_C1-Pad1)") (class "Default")
      (node (ref "EPD_C1") (pin "1") (pinfunction "1_1") (pintype "passive"))
      (node (ref "J1") (pin "4") (pinfunction "4_4") (pintype "bidirectional"))
    )
    (net (code "26") (name "Net-(EPD_C2-Pad1)") (class "Default")
      (node (ref "EPD_C2") (pin "1") (pinfunction "1_1") (pintype "passive"))
      (node (ref "J1") (pin "5") (pinfunction "5_5") (pintype "bidirectional"))
    )
    (net (code "27") (name "Net-(EPD_C6-Pad1)") (class "Default")
      (node (ref "EPD_C6") (pin "1") (pinfunction "1_1") (pintype "passive"))
      (node (ref "J1") (pin "18") (pinfunction "18_18") (pintype "bidirectional"))
    )
    (net (code "28") (name "Net-(EPD_C7-Pad1)") (class "Default")
      (node (ref "EPD_C7") (pin "1") (pinfunction "1_1") (pintype "passive"))
      (node (ref "J1") (pin "19") (pinfunction "19_19") (pintype "bidirectional"))
    )
    (net (code "29") (name "Net-(EPD_C8-Pad1)") (class "Default")
      (node (ref "EPD_C8") (pin "1") (pinfunction "1_1") (pintype "passive"))
      (node (ref "J1") (pin "20") (pinfunction "20_20") (pintype "bidirectional"))
    )
    (net (code "30") (name "Net-(EPD_C10-Pad1)") (class "Default")
      (node (ref "EPD_C10") (pin "1") (pinfunction "1_1") (pintype "passive"))
      (node (ref "J1") (pin "22") (pinfunction "22_22") (pintype "bidirectional"))
    )
    (net (code "31") (name "Net-(EPD_C12-Pad1)") (class "Default")
      (node (ref "EPD_C12") (pin "1") (pinfunction "1_1") (pintype "passive"))
      (node (ref "J1") (pin "24") (pinfunction "24_24") (pintype "bidirectional"))
    )
    (net (code "32") (name "Net-(IC1-CT)") (class "Default")
      (node (ref "C_DELAY") (pin "1") (pinfunction "1_1") (pintype "passive"))
      (node (ref "IC1") (pin "5") (pinfunction "CT_5") (pintype "bidirectional"))
    )
    (net (code "33") (name "Net-(J2-PadA5)") (class "Default")
      (node (ref "J2") (pin "A5") (pinfunction "A5_A5") (pintype "bidirectional"))
      (node (ref "R2-USB1") (pin "2") (pinfunction "2_2") (pintype "passive"))
    )
    (net (code "34") (name "Net-(J2-PadB5)") (class "Default")
      (node (ref "J2") (pin "B5") (pinfunction "B5_B5") (pintype "bidirectional"))
      (node (ref "R2-USB") (pin "1") (pinfunction "1_1") (pintype "passive"))
    )
    (net (code "35") (name "Net-(MCP73831-PROG)") (class "Default")
      (node (ref "MCP73831") (pin "5") (pinfunction "PROG_5") (pintype "input"))
      (node (ref "R2_BAT") (pin "2") (pinfunction "2_2") (pintype "passive"))
    )
    (net (code "36") (name "Net-(MCP73831-STAT)") (class "Default")
      (node (ref "MCP73831") (pin "1") (pinfunction "STAT_1") (pintype "output"))
      (node (ref "R1_BAT") (pin "1") (pinfunction "1_1") (pintype "passive"))
    )
    (net (code "37") (name "PREVGH") (class "Default")
      (node (ref "D5") (pin "1") (pinfunction "K_1") (pintype "bidirectional"))
      (node (ref "EPD_C9") (pin "1") (pinfunction "1_1") (pintype "passive"))
      (node (ref "J1") (pin "21") (pinfunction "21_21") (pintype "bidirectional"))
    )
    (net (code "38") (name "PREVGL") (class "Default")
      (node (ref "D4") (pin "2") (pinfunction "A_2") (pintype "bidirectional"))
      (node (ref "EPD_C11") (pin "1") (pinfunction "1_1") (pintype "passive"))
      (node (ref "J1") (pin "23") (pinfunction "23_23") (pintype "bidirectional"))
    )
    (net (code "39") (name "RESE") (class "Default")
      (node (ref "J1") (pin "3") (pinfunction "3_3") (pintype "bidirectional"))
      (node (ref "Q3") (pin "2") (pinfunction "S_2") (pintype "bidirectional"))
      (node (ref "R3") (pin "2") (pinfunction "2_2") (pintype "passive"))
    )
    (net (code "40") (name "RESE'") (class "Default")
      (node (ref "R2") (pin "2") (pinfunction "2_2") (pintype "passive"))
      (node (ref "R3") (pin "1") (pinfunction "1_1") (pintype "passive"))
      (node (ref "SJ1") (pin "2") (pinfunction "2_2") (pintype "passive"))
    )
    (net (code "41") (name "RESET") (class "Default")
      (node (ref "C5") (pin "1") (pinfunction "1_1") (pintype "passive"))
      (node (ref "IC1") (pin "1") (pinfunction "VOUT_1") (pintype "bidirectional"))
      (node (ref "RESET_BUTTON") (pin "3") (pinfunction "3_3") (pintype "passive"))
      (node (ref "RESET_BUTTON") (pin "4") (pinfunction "4_4") (pintype "passive"))
      (node (ref "R_RESET") (pin "2") (pinfunction "2_2") (pintype "passive"))
      (node (ref "U2") (pin "3") (pinfunction "EN_3") (pintype "input"))
    )
    (net (code "42") (name "RTC_RST") (class "Default")
      (node (ref "U2") (pin "16") (pinfunction "IO18_16") (pintype "bidirectional"))
      (node (ref "U3") (pin "4") (pinfunction "~{RST}_4") (pintype "input"))
    )
    (net (code "43") (name "RX") (class "Default")
      (node (ref "TP2") (pin "TP") (pinfunction "TP_TP") (pintype "input"))
      (node (ref "U2") (pin "24") (pinfunction "RXD0/GPIO17_24") (pintype "bidirectional"))
    )
    (net (code "44") (name "SCK") (class "Default")
      (node (ref "D10") (pin "1") (pinfunction "1_1") (pintype "passive"))
      (node (ref "J1") (pin "13") (pinfunction "13_13") (pintype "bidirectional"))
      (node (ref "J4") (pin "P5") (pinfunction "CLK_P5") (pintype "bidirectional"))
      (node (ref "R6") (pin "1") (pinfunction "1_1") (pintype "passive"))
      (node (ref "TP8") (pin "TP") (pinfunction "TP_TP") (pintype "input"))
      (node (ref "U1") (pin "6") (pinfunction "CLK_6") (pintype "input"))
      (node (ref "U2") (pin "6") (pinfunction "IO6_6") (pintype "bidirectional"))
    )
    (net (code "45") (name "SCL") (class "Default")
      (node (ref "J3") (pin "4") (pinfunction "4_4") (pintype "passive"))
      (node (ref "R2-PINH") (pin "1") (pinfunction "1_1") (pintype "passive"))
      (node (ref "SENSOR2") (pin "4") (pinfunction "SCK_4") (pintype "input"))
      (node (ref "U2") (pin "20") (pinfunction "IO22_20") (pintype "bidirectional"))
      (node (ref "U3") (pin "16") (pinfunction "SCL_16") (pintype "input"))
      (node (ref "U4") (pin "7") (pinfunction "SCL_7") (pintype "input"))
    )
    (net (code "46") (name "SDA") (class "Default")
      (node (ref "J3") (pin "3") (pinfunction "3_3") (pintype "passive"))
      (node (ref "R1_PINH") (pin "1") (pinfunction "1_1") (pintype "passive"))
      (node (ref "SENSOR2") (pin "3") (pinfunction "SDI_3") (pintype "bidirectional"))
      (node (ref "U2") (pin "19") (pinfunction "IO21_19") (pintype "bidirectional"))
      (node (ref "U3") (pin "15") (pinfunction "SDA_15") (pintype "bidirectional"))
      (node (ref "U4") (pin "8") (pinfunction "SDA_8") (pintype "bidirectional"))
    )
    (net (code "47") (name "SRC") (class "Default")
      (node (ref "C4") (pin "2") (pinfunction "2_2") (pintype "passive"))
      (node (ref "D5") (pin "2") (pinfunction "A_2") (pintype "bidirectional"))
      (node (ref "L1") (pin "1") (pinfunction "1_1") (pintype "passive"))
      (node (ref "Q3") (pin "3") (pinfunction "D_3") (pintype "bidirectional"))
    )
    (net (code "48") (name "SS_SD") (class "Default")
      (node (ref "D8") (pin "1") (pinfunction "1_1") (pintype "passive"))
      (node (ref "J4") (pin "P2") (pinfunction "CD/DAT3_P2") (pintype "bidirectional"))
      (node (ref "R10") (pin "1") (pinfunction "1_1") (pintype "passive"))
      (node (ref "U2") (pin "4") (pinfunction "IO4_4") (pintype "bidirectional"))
    )
    (net (code "49") (name "TX") (class "Default")
      (node (ref "TP1") (pin "TP") (pinfunction "TP_TP") (pintype "input"))
      (node (ref "U2") (pin "25") (pinfunction "TXD0/GPIO16_25") (pintype "bidirectional"))
    )
    (net (code "50") (name "USB_D+") (class "Default")
      (node (ref "D1") (pin "1") (pinfunction "I/O1_1_1") (pintype "bidirectional"))
      (node (ref "U2") (pin "14") (pinfunction "IO13_14") (pintype "bidirectional"))
    )
    (net (code "51") (name "USB_D-") (class "Default")
      (node (ref "D1") (pin "3") (pinfunction "I/O2_1_3") (pintype "bidirectional"))
      (node (ref "U2") (pin "13") (pinfunction "IO12_13") (pintype "bidirectional"))
    )
    (net (code "52") (name "VBAT") (class "Default")
      (node (ref "C2_BAT") (pin "1") (pinfunction "1_1") (pintype "passive"))
      (node (ref "MCP73831") (pin "3") (pinfunction "VBAT_3") (pintype "power_in"))
      (node (ref "Q1") (pin "3") (pinfunction "D_3") (pintype "bidirectional"))
      (node (ref "TP3") (pin "TP") (pinfunction "TP_TP") (pintype "input"))
      (node (ref "U4") (pin "2") (pinfunction "CELL_2") (pintype "power_in"))
      (node (ref "U4") (pin "3") (pinfunction "VDD_3") (pintype "power_in"))
    )
    (net (code "53") (name "VBUS") (class "Default")
      (node (ref "C1_BAT") (pin "1") (pinfunction "1_1") (pintype "passive"))
      (node (ref "C4_USB") (pin "1") (pinfunction "1_1") (pintype "passive"))
      (node (ref "C5_USB") (pin "1") (pinfunction "1_1") (pintype "passive"))
      (node (ref "CHG_LED") (pin "A") (pinfunction "A_A") (pintype "passive"))
      (node (ref "D1") (pin "5") (pinfunction "VBUS_5") (pintype "bidirectional"))
      (node (ref "D2") (pin "2") (pinfunction "ANODE_2") (pintype "bidirectional"))
      (node (ref "MCP73831") (pin "4") (pinfunction "VIN_4") (pintype "power_in"))
      (node (ref "PFMF.050.1") (pin "2") (pinfunction "2_2") (pintype "passive"))
      (node (ref "Q1") (pin "1") (pinfunction "G_1") (pintype "bidirectional"))
      (node (ref "R1_PWRUSB") (pin "2") (pinfunction "2_2") (pintype "passive"))
      (node (ref "TP14") (pin "TP") (pinfunction "TP_TP") (pintype "input"))
    )
    (net (code "54") (name "VRTC") (class "Default")
      (node (ref "C10_SUPERCAP") (pin "2") (pinfunction "2_2") (pintype "passive"))
      (node (ref "C8") (pin "1") (pinfunction "1_1") (pintype "passive"))
      (node (ref "R_CAPACITOR") (pin "1") (pinfunction "1_1") (pintype "passive"))
      (node (ref "U3") (pin "14") (pinfunction "VBAT_14") (pintype "power_in"))
    )
    (net (code "55") (name "VUSB") (class "Default")
      (node (ref "J2") (pin "A4") (pinfunction "A4_A4") (pintype "bidirectional"))
      (node (ref "J2") (pin "A9") (pinfunction "A9_A9") (pintype "bidirectional"))
      (node (ref "J2") (pin "B4") (pinfunction "B4_B4") (pintype "bidirectional"))
      (node (ref "J2") (pin "B9") (pinfunction "B9_B9") (pintype "bidirectional"))
      (node (ref "PFMF.050.1") (pin "1") (pinfunction "1_1") (pintype "passive"))
    )
    (net (code "56") (name "unconnected-(IC1-NC-Pad4)") (class "Default")
      (node (ref "IC1") (pin "4") (pinfunction "NC_4") (pintype "no_connect"))
    )
    (net (code "57") (name "unconnected-(IC4-NC-Pad4)") (class "Default")
      (node (ref "IC4") (pin "4") (pinfunction "NC_4") (pintype "no_connect"))
    )
    (net (code "58") (name "unconnected-(J1-Pad1)") (class "Default")
      (node (ref "J1") (pin "1") (pinfunction "1_1") (pintype "bidirectional"))
    )
    (net (code "59") (name "unconnected-(J1-Pad6)") (class "Default")
      (node (ref "J1") (pin "6") (pinfunction "6_6") (pintype "bidirectional"))
    )
    (net (code "60") (name "unconnected-(J1-Pad7)") (class "Default")
      (node (ref "J1") (pin "7") (pinfunction "7_7") (pintype "bidirectional"))
    )
    (net (code "61") (name "unconnected-(J2-PadA8)") (class "Default")
      (node (ref "J2") (pin "A8") (pinfunction "A8_A8") (pintype "bidirectional"))
    )
    (net (code "62") (name "unconnected-(J2-PadB8)") (class "Default")
      (node (ref "J2") (pin "B8") (pinfunction "B8_B8") (pintype "bidirectional"))
    )
    (net (code "63") (name "unconnected-(J4-DAT1-PadP8)") (class "Default")
      (node (ref "J4") (pin "P8") (pinfunction "DAT1_P8") (pintype "bidirectional"))
    )
    (net (code "64") (name "unconnected-(J4-DAT2-PadP1)") (class "Default")
      (node (ref "J4") (pin "P1") (pinfunction "DAT2_P1") (pintype "bidirectional"))
    )
    (net (code "65") (name "unconnected-(J4-DETECTION_1-PadS1)") (class "Default")
      (node (ref "J4") (pin "S1") (pinfunction "DETECTION_1_S1") (pintype "bidirectional"))
    )
    (net (code "66") (name "unconnected-(J4-DETECTION_2-PadS2)") (class "Default")
      (node (ref "J4") (pin "S2") (pinfunction "DETECTION_2_S2") (pintype "bidirectional"))
    )
    (net (code "67") (name "unconnected-(U2-NC-Pad22)") (class "Default")
      (node (ref "U2") (pin "22") (pinfunction "NC_22") (pintype "no_connect"))
    )
    (net (code "68") (name "unconnected-(U4-~{ALERT}-Pad5)") (class "Default")
      (node (ref "U4") (pin "5") (pinfunction "~{ALERT}_5") (pintype "output"))
    )
  )
)
